# FULL_CB_Plugs_REV_C.net
KiCad netlist of a schematic drawn in Altium Designer
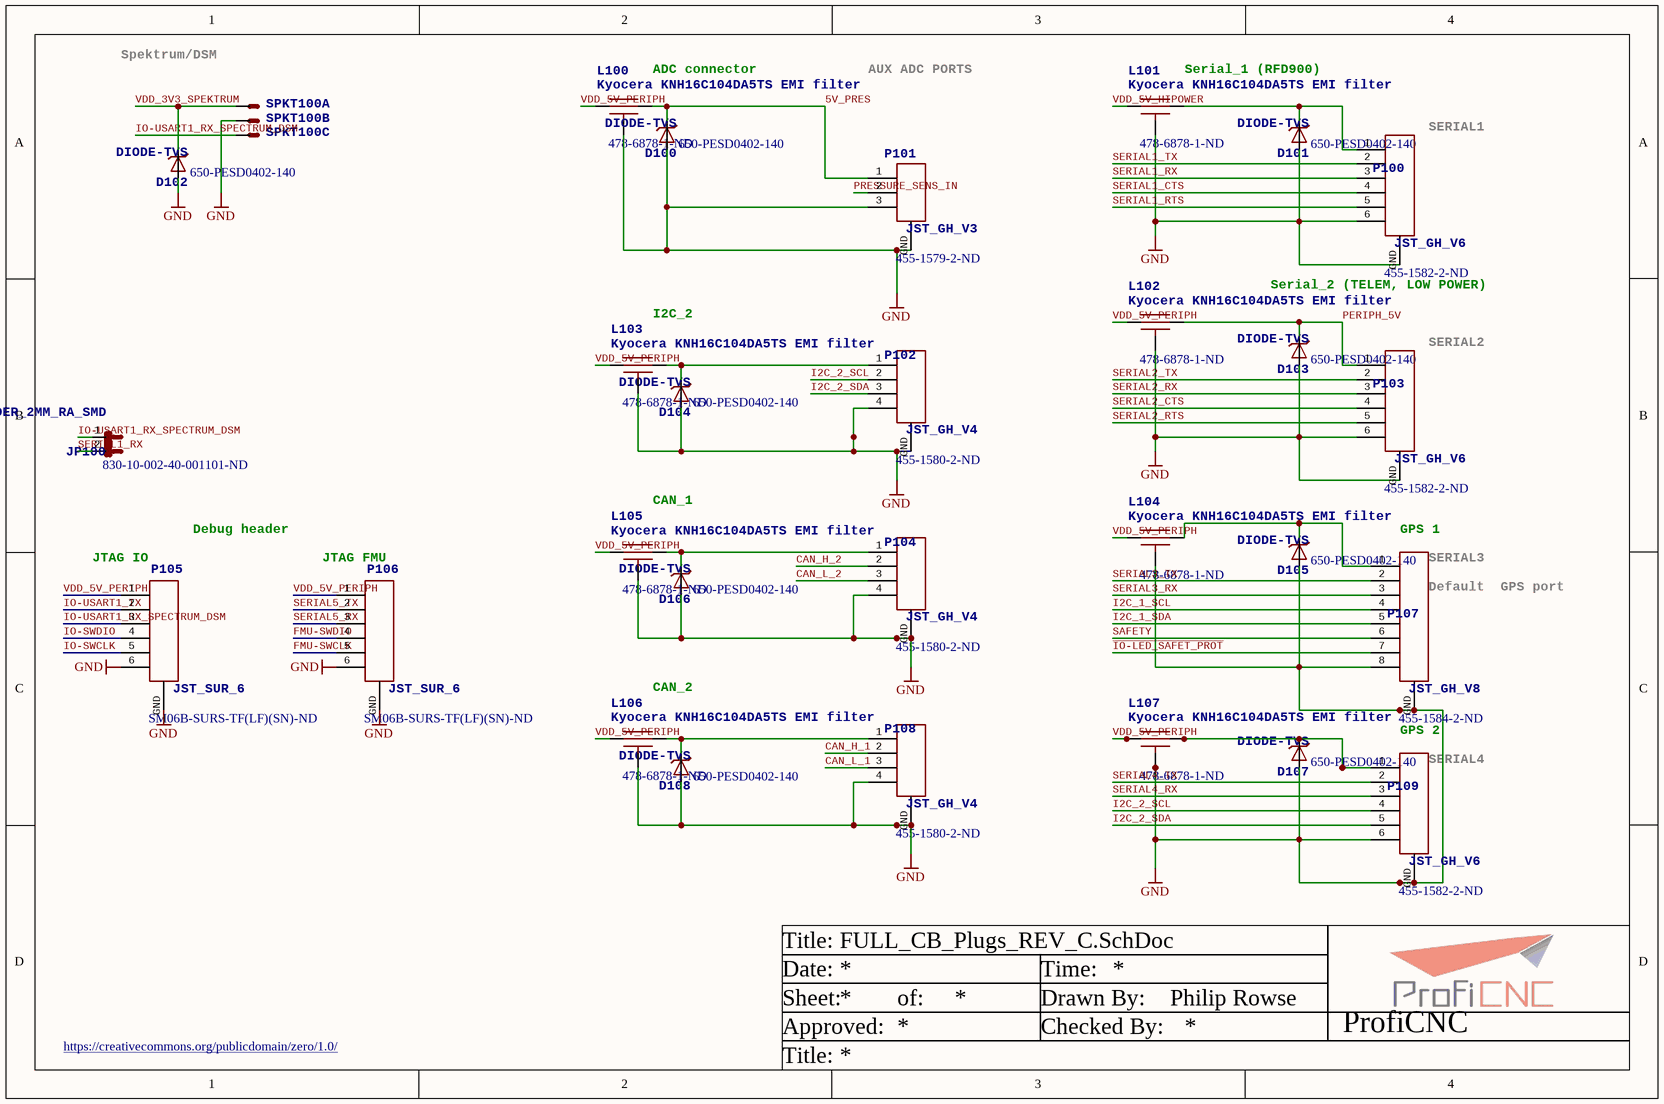
[diagram p0: FULL_CB_Plugs_REV_C.SchDoc]

(export (version "E")
  (design (tool "Eeschema 10.0.6"))
  (components
    (comp (ref "D100")
      (value "DIODE-TVS")
      (footprint "0402-TVS")
      (description "Diode, TVS, 14VWM, 40VC, 0402, SMD")
      (fields (field (name "SUPPLIER PART NUMBER 1") "650-PESD0402-140"))
      (libsource (lib "CB_REV_C") (part "DIODE-TVS"))
    )
    (comp (ref "D101")
      (value "DIODE-TVS")
      (footprint "0402-TVS")
      (description "Diode, TVS, 14VWM, 40VC, 0402, SMD")
      (fields (field (name "SUPPLIER PART NUMBER 1") "650-PESD0402-140"))
      (libsource (lib "CB_REV_C") (part "DIODE-TVS"))
    )
    (comp (ref "D102")
      (value "DIODE-TVS")
      (footprint "0402-TVS")
      (description "Diode, TVS, 14VWM, 40VC, 0402, SMD")
      (fields (field (name "SUPPLIER PART NUMBER 1") "650-PESD0402-140"))
      (libsource (lib "CB_REV_C") (part "DIODE-TVS"))
    )
    (comp (ref "D103")
      (value "DIODE-TVS")
      (footprint "0402-TVS")
      (description "Diode, TVS, 14VWM, 40VC, 0402, SMD")
      (fields (field (name "SUPPLIER PART NUMBER 1") "650-PESD0402-140"))
      (libsource (lib "CB_REV_C") (part "DIODE-TVS"))
    )
    (comp (ref "D104")
      (value "DIODE-TVS")
      (footprint "0402-TVS")
      (description "Diode, TVS, 14VWM, 40VC, 0402, SMD")
      (fields (field (name "SUPPLIER PART NUMBER 1") "650-PESD0402-140"))
      (libsource (lib "CB_REV_C") (part "DIODE-TVS"))
    )
    (comp (ref "D105")
      (value "DIODE-TVS")
      (footprint "0402-TVS")
      (description "Diode, TVS, 14VWM, 40VC, 0402, SMD")
      (fields (field (name "SUPPLIER PART NUMBER 1") "650-PESD0402-140"))
      (libsource (lib "CB_REV_C") (part "DIODE-TVS"))
    )
    (comp (ref "D106")
      (value "DIODE-TVS")
      (footprint "0402-TVS")
      (description "Diode, TVS, 14VWM, 40VC, 0402, SMD")
      (fields (field (name "SUPPLIER PART NUMBER 1") "650-PESD0402-140"))
      (libsource (lib "CB_REV_C") (part "DIODE-TVS"))
    )
    (comp (ref "D107")
      (value "DIODE-TVS")
      (footprint "0402-TVS")
      (description "Diode, TVS, 14VWM, 40VC, 0402, SMD")
      (fields (field (name "SUPPLIER PART NUMBER 1") "650-PESD0402-140"))
      (libsource (lib "CB_REV_C") (part "DIODE-TVS"))
    )
    (comp (ref "D108")
      (value "DIODE-TVS")
      (footprint "0402-TVS")
      (description "Diode, TVS, 14VWM, 40VC, 0402, SMD")
      (fields (field (name "SUPPLIER PART NUMBER 1") "650-PESD0402-140"))
      (libsource (lib "CB_REV_C") (part "DIODE-TVS"))
    )
    (comp (ref "JP100")
      (value "HEADER_2MM_RA_SMD")
      (footprint "HEADER_2MM_RA_2")
      (description "Connector, PCB, 2MM, 2Pos, R/A, SMD, Au")
      (fields (field (name "SUPPLIER PART NUMBER 1") "830-10-002-40-001101-ND"))
      (libsource (lib "CB_REV_C") (part "HEADER_2MM_RA_SMD"))
    )
    (comp (ref "L100")
      (value "Kyocera KNH16C104DA5TS EMI filter")
      (footprint "KYOCERA-KNH16-DA")
      (description "Capacitor, Filter, 0.1uF, 25V, 2A, 0603, SMD")
      (fields (field (name "SUPPLIER PART NUMBER 1") "478-6878-1-ND"))
      (libsource (lib "CB_REV_C") (part "KNH16C104DA5TS"))
    )
    (comp (ref "L101")
      (value "Kyocera KNH16C104DA5TS EMI filter")
      (footprint "KYOCERA-KNH16-DA")
      (description "Capacitor, Filter, 0.1uF, 25V, 2A, 0603, SMD")
      (fields (field (name "SUPPLIER PART NUMBER 1") "478-6878-1-ND"))
      (libsource (lib "CB_REV_C") (part "KNH16C104DA5TS"))
    )
    (comp (ref "L102")
      (value "Kyocera KNH16C104DA5TS EMI filter")
      (footprint "KYOCERA-KNH16-DA")
      (description "Capacitor, Filter, 0.1uF, 25V, 2A, 0603, SMD")
      (fields (field (name "SUPPLIER PART NUMBER 1") "478-6878-1-ND"))
      (libsource (lib "CB_REV_C") (part "KNH16C104DA5TS"))
    )
    (comp (ref "L103")
      (value "Kyocera KNH16C104DA5TS EMI filter")
      (footprint "KYOCERA-KNH16-DA")
      (description "Capacitor, Filter, 0.1uF, 25V, 2A, 0603, SMD")
      (fields (field (name "SUPPLIER PART NUMBER 1") "478-6878-1-ND"))
      (libsource (lib "CB_REV_C") (part "KNH16C104DA5TS"))
    )
    (comp (ref "L104")
      (value "Kyocera KNH16C104DA5TS EMI filter")
      (footprint "KYOCERA-KNH16-DA")
      (description "Capacitor, Filter, 0.1uF, 25V, 2A, 0603, SMD")
      (fields (field (name "SUPPLIER PART NUMBER 1") "478-6878-1-ND"))
      (libsource (lib "CB_REV_C") (part "KNH16C104DA5TS"))
    )
    (comp (ref "L105")
      (value "Kyocera KNH16C104DA5TS EMI filter")
      (footprint "KYOCERA-KNH16-DA")
      (description "Capacitor, Filter, 0.1uF, 25V, 2A, 0603, SMD")
      (fields (field (name "SUPPLIER PART NUMBER 1") "478-6878-1-ND"))
      (libsource (lib "CB_REV_C") (part "KNH16C104DA5TS"))
    )
    (comp (ref "L106")
      (value "Kyocera KNH16C104DA5TS EMI filter")
      (footprint "KYOCERA-KNH16-DA")
      (description "Capacitor, Filter, 0.1uF, 25V, 2A, 0603, SMD")
      (fields (field (name "SUPPLIER PART NUMBER 1") "478-6878-1-ND"))
      (libsource (lib "CB_REV_C") (part "KNH16C104DA5TS"))
    )
    (comp (ref "L107")
      (value "Kyocera KNH16C104DA5TS EMI filter")
      (footprint "KYOCERA-KNH16-DA")
      (description "Capacitor, Filter, 0.1uF, 25V, 2A, 0603, SMD")
      (fields (field (name "SUPPLIER PART NUMBER 1") "478-6878-1-ND"))
      (libsource (lib "CB_REV_C") (part "KNH16C104DA5TS"))
    )
    (comp (ref "P100")
      (value "JST_GH_V6")
      (footprint "JST_GH_V6")
      (description "BM06B-GHS-TBT")
      (fields (field (name "SUPPLIER PART NUMBER 1") "455-1582-2-ND"))
      (libsource (lib "CB_REV_C") (part "JST_GH_V6"))
    )
    (comp (ref "P101")
      (value "JST_GH_V3")
      (footprint "JST_GH_V3")
      (description "BM03B-GHS-TBT")
      (fields (field (name "SUPPLIER PART NUMBER 1") "455-1579-2-ND"))
      (libsource (lib "CB_REV_C") (part "JST_GH_V3"))
    )
    (comp (ref "P102")
      (value "JST_GH_V4")
      (footprint "JST_GH_V4")
      (description "BM04B-GHS-TBT")
      (fields (field (name "SUPPLIER PART NUMBER 1") "455-1580-2-ND"))
      (libsource (lib "CB_REV_C") (part "JST_GH_V4"))
    )
    (comp (ref "P103")
      (value "JST_GH_V6")
      (footprint "JST_GH_V6")
      (description "BM06B-GHS-TBT")
      (fields (field (name "SUPPLIER PART NUMBER 1") "455-1582-2-ND"))
      (libsource (lib "CB_REV_C") (part "JST_GH_V6"))
    )
    (comp (ref "P104")
      (value "JST_GH_V4")
      (footprint "JST_GH_V4")
      (description "BM04B-GHS-TBT")
      (fields (field (name "SUPPLIER PART NUMBER 1") "455-1580-2-ND"))
      (libsource (lib "CB_REV_C") (part "JST_GH_V4"))
    )
    (comp (ref "P105")
      (value "JST_SUR_6")
      (footprint "JST_SUR_H6")
      (description "Connector, Header, 6Pos, .8mm IDC, R/A, SMD, Tin")
      (fields (field (name "SUPPLIER PART NUMBER 1") "SM06B-SURS-TF(LF)(SN)-ND"))
      (libsource (lib "CB_REV_C") (part "JST_SUR_6"))
    )
    (comp (ref "P106")
      (value "JST_SUR_6")
      (footprint "JST_SUR_H6")
      (description "Connector, Header, 6Pos, .8mm IDC, R/A, SMD, Tin")
      (fields (field (name "SUPPLIER PART NUMBER 1") "SM06B-SURS-TF(LF)(SN)-ND"))
      (libsource (lib "CB_REV_C") (part "JST_SUR_6"))
    )
    (comp (ref "P107")
      (value "JST_GH_V8")
      (footprint "JST_GH_V8")
      (description "BM08B-GHS-TBT")
      (fields (field (name "SUPPLIER PART NUMBER 1") "455-1584-2-ND"))
      (libsource (lib "CB_REV_C") (part "JST_GH_V8"))
    )
    (comp (ref "P108")
      (value "JST_GH_V4")
      (footprint "JST_GH_V4")
      (description "BM04B-GHS-TBT")
      (fields (field (name "SUPPLIER PART NUMBER 1") "455-1580-2-ND"))
      (libsource (lib "CB_REV_C") (part "JST_GH_V4"))
    )
    (comp (ref "P109")
      (value "JST_GH_V6")
      (footprint "JST_GH_V6")
      (description "BM06B-GHS-TBT")
      (fields (field (name "SUPPLIER PART NUMBER 1") "455-1582-2-ND"))
      (libsource (lib "CB_REV_C") (part "JST_GH_V6"))
    )
    (comp (ref "SPKT100")
      (value "CONN_SPEKTRUM_RX-TH")
      (footprint "B3B-ZR")
      (description "Spektrum RX connector; JST ZH series S3B-ZR-SM4A-TF")
      (fields (field (name "PARTNO") "B3B-ZR(LF)(SN)"))
      (libsource (lib "CB_REV_C") (part "CONN_SPEKTRUM_RX-TH"))
    )
  )
  (nets
    (net (code "1") (name "/5V_PRES") (class "Default")
      (node (ref "D100") (pin "C") (pinfunction "C_C") (pintype "passive"))
      (node (ref "L100") (pin "P$2") (pinfunction "P$2_P$2") (pintype "passive"))
      (node (ref "P101") (pin "1") (pinfunction "1_1") (pintype "passive"))
    )
    (net (code "2") (name "/CAN_H_1") (class "Default")
      (node (ref "P108") (pin "2") (pinfunction "2_2") (pintype "passive"))
    )
    (net (code "3") (name "/CAN_H_2") (class "Default")
      (node (ref "P104") (pin "2") (pinfunction "2_2") (pintype "passive"))
    )
    (net (code "4") (name "/CAN_L_1") (class "Default")
      (node (ref "P108") (pin "3") (pinfunction "3_3") (pintype "passive"))
    )
    (net (code "5") (name "/CAN_L_2") (class "Default")
      (node (ref "P104") (pin "3") (pinfunction "3_3") (pintype "passive"))
    )
    (net (code "6") (name "/FMU-SWCLK") (class "Default")
      (node (ref "P106") (pin "5") (pinfunction "5_5") (pintype "passive"))
    )
    (net (code "7") (name "/FMU-SWDIO") (class "Default")
      (node (ref "P106") (pin "4") (pinfunction "4_4") (pintype "passive"))
    )
    (net (code "8") (name "/I2C_1_SCL") (class "Default")
      (node (ref "P107") (pin "4") (pinfunction "4_4") (pintype "passive"))
    )
    (net (code "9") (name "/I2C_1_SDA") (class "Default")
      (node (ref "P107") (pin "5") (pinfunction "5_5") (pintype "passive"))
    )
    (net (code "10") (name "/I2C_2_SCL") (class "Default")
      (node (ref "P102") (pin "2") (pinfunction "2_2") (pintype "passive"))
      (node (ref "P109") (pin "4") (pinfunction "4_4") (pintype "passive"))
    )
    (net (code "11") (name "/I2C_2_SDA") (class "Default")
      (node (ref "P102") (pin "3") (pinfunction "3_3") (pintype "passive"))
      (node (ref "P109") (pin "5") (pinfunction "5_5") (pintype "passive"))
    )
    (net (code "12") (name "/IO-SWCLK") (class "Default")
      (node (ref "P105") (pin "5") (pinfunction "5_5") (pintype "passive"))
    )
    (net (code "13") (name "/IO-SWDIO") (class "Default")
      (node (ref "P105") (pin "4") (pinfunction "4_4") (pintype "passive"))
    )
    (net (code "14") (name "/IO-USART1_RX_SPECTRUM_DSM") (class "Default")
      (node (ref "JP100") (pin "1") (pinfunction "1_1") (pintype "passive"))
      (node (ref "P105") (pin "3") (pinfunction "3_3") (pintype "passive"))
      (node (ref "SPKT100") (pin "1") (pinfunction "S_1") (pintype "passive"))
    )
    (net (code "15") (name "/IO-USART1_TX") (class "Default")
      (node (ref "P105") (pin "2") (pinfunction "2_2") (pintype "passive"))
    )
    (net (code "16") (name "/PERIPH_5V") (class "Default")
      (node (ref "D103") (pin "C") (pinfunction "C_C") (pintype "passive"))
      (node (ref "L102") (pin "P$2") (pinfunction "P$2_P$2") (pintype "passive"))
      (node (ref "P103") (pin "1") (pinfunction "1_1") (pintype "passive"))
    )
    (net (code "17") (name "/PRESSURE_SENS_IN") (class "Default")
      (node (ref "P101") (pin "2") (pinfunction "2_2") (pintype "passive"))
    )
    (net (code "18") (name "/SAFETY") (class "Default")
      (node (ref "P107") (pin "6") (pinfunction "6_6") (pintype "passive"))
    )
    (net (code "19") (name "/SERIAL1_CTS") (class "Default")
      (node (ref "P100") (pin "4") (pinfunction "4_4") (pintype "passive"))
    )
    (net (code "20") (name "/SERIAL1_RTS") (class "Default")
      (node (ref "P100") (pin "5") (pinfunction "5_5") (pintype "passive"))
    )
    (net (code "21") (name "/SERIAL1_RX") (class "Default")
      (node (ref "JP100") (pin "2") (pinfunction "2_2") (pintype "passive"))
      (node (ref "P100") (pin "3") (pinfunction "3_3") (pintype "passive"))
    )
    (net (code "22") (name "/SERIAL1_TX") (class "Default")
      (node (ref "P100") (pin "2") (pinfunction "2_2") (pintype "passive"))
    )
    (net (code "23") (name "/SERIAL2_CTS") (class "Default")
      (node (ref "P103") (pin "4") (pinfunction "4_4") (pintype "passive"))
    )
    (net (code "24") (name "/SERIAL2_RTS") (class "Default")
      (node (ref "P103") (pin "5") (pinfunction "5_5") (pintype "passive"))
    )
    (net (code "25") (name "/SERIAL2_RX") (class "Default")
      (node (ref "P103") (pin "3") (pinfunction "3_3") (pintype "passive"))
    )
    (net (code "26") (name "/SERIAL2_TX") (class "Default")
      (node (ref "P103") (pin "2") (pinfunction "2_2") (pintype "passive"))
    )
    (net (code "27") (name "/SERIAL3_RX") (class "Default")
      (node (ref "P107") (pin "3") (pinfunction "3_3") (pintype "passive"))
    )
    (net (code "28") (name "/SERIAL3_TX") (class "Default")
      (node (ref "P107") (pin "2") (pinfunction "2_2") (pintype "passive"))
    )
    (net (code "29") (name "/SERIAL4_RX") (class "Default")
      (node (ref "P109") (pin "3") (pinfunction "3_3") (pintype "passive"))
    )
    (net (code "30") (name "/SERIAL4_TX") (class "Default")
      (node (ref "P109") (pin "2") (pinfunction "2_2") (pintype "passive"))
    )
    (net (code "31") (name "/SERIAL5_RX") (class "Default")
      (node (ref "P106") (pin "3") (pinfunction "3_3") (pintype "passive"))
    )
    (net (code "32") (name "/SERIAL5_TX") (class "Default")
      (node (ref "P106") (pin "2") (pinfunction "2_2") (pintype "passive"))
    )
    (net (code "33") (name "/VDD_3V3_SPEKTRUM") (class "Default")
      (node (ref "D102") (pin "C") (pinfunction "C_C") (pintype "passive"))
      (node (ref "SPKT100") (pin "3") (pinfunction "S_3") (pintype "passive"))
    )
    (net (code "34") (name "/VDD_5V_HIPOWER") (class "Default")
      (node (ref "L101") (pin "P$1") (pinfunction "P$1_P$1") (pintype "passive"))
    )
    (net (code "35") (name "/VDD_5V_PERIPH") (class "Default")
      (node (ref "L100") (pin "P$1") (pinfunction "P$1_P$1") (pintype "passive"))
      (node (ref "L102") (pin "P$1") (pinfunction "P$1_P$1") (pintype "passive"))
      (node (ref "L103") (pin "P$1") (pinfunction "P$1_P$1") (pintype "passive"))
      (node (ref "L104") (pin "P$1") (pinfunction "P$1_P$1") (pintype "passive"))
      (node (ref "L105") (pin "P$1") (pinfunction "P$1_P$1") (pintype "passive"))
      (node (ref "L106") (pin "P$1") (pinfunction "P$1_P$1") (pintype "passive"))
      (node (ref "L107") (pin "P$1") (pinfunction "P$1_P$1") (pintype "passive"))
      (node (ref "P105") (pin "1") (pinfunction "1_1") (pintype "passive"))
      (node (ref "P106") (pin "1") (pinfunction "1_1") (pintype "passive"))
    )
    (net (code "36") (name "/~{IO-LED_SAFET_PROT}") (class "Default")
      (node (ref "P107") (pin "7") (pinfunction "7_7") (pintype "passive"))
    )
    (net (code "37") (name "GND") (class "Default")
      (node (ref "D100") (pin "A") (pinfunction "A_A") (pintype "passive"))
      (node (ref "D101") (pin "A") (pinfunction "A_A") (pintype "passive"))
      (node (ref "D102") (pin "A") (pinfunction "A_A") (pintype "passive"))
      (node (ref "D103") (pin "A") (pinfunction "A_A") (pintype "passive"))
      (node (ref "D104") (pin "A") (pinfunction "A_A") (pintype "passive"))
      (node (ref "D105") (pin "A") (pinfunction "A_A") (pintype "passive"))
      (node (ref "D106") (pin "A") (pinfunction "A_A") (pintype "passive"))
      (node (ref "D107") (pin "A") (pinfunction "A_A") (pintype "passive"))
      (node (ref "D108") (pin "A") (pinfunction "A_A") (pintype "passive"))
      (node (ref "L100") (pin "GND") (pinfunction "GND_GND") (pintype "passive"))
      (node (ref "L101") (pin "GND") (pinfunction "GND_GND") (pintype "passive"))
      (node (ref "L102") (pin "GND") (pinfunction "GND_GND") (pintype "passive"))
      (node (ref "L103") (pin "GND") (pinfunction "GND_GND") (pintype "passive"))
      (node (ref "L104") (pin "GND") (pinfunction "GND_GND") (pintype "passive"))
      (node (ref "L105") (pin "GND") (pinfunction "GND_GND") (pintype "passive"))
      (node (ref "L106") (pin "GND") (pinfunction "GND_GND") (pintype "passive"))
      (node (ref "L107") (pin "GND") (pinfunction "GND_GND") (pintype "passive"))
      (node (ref "P100") (pin "6") (pinfunction "6_6") (pintype "passive"))
      (node (ref "P100") (pin "GND") (pinfunction "GND_GND") (pintype "passive"))
      (node (ref "P101") (pin "3") (pinfunction "3_3") (pintype "passive"))
      (node (ref "P101") (pin "GND") (pinfunction "GND_GND") (pintype "passive"))
      (node (ref "P102") (pin "4") (pinfunction "4_4") (pintype "passive"))
      (node (ref "P102") (pin "GND") (pinfunction "GND_GND") (pintype "passive"))
      (node (ref "P103") (pin "6") (pinfunction "6_6") (pintype "passive"))
      (node (ref "P103") (pin "GND") (pinfunction "GND_GND") (pintype "passive"))
      (node (ref "P104") (pin "4") (pinfunction "4_4") (pintype "passive"))
      (node (ref "P104") (pin "GND") (pinfunction "GND_GND") (pintype "passive"))
      (node (ref "P105") (pin "6") (pinfunction "6_6") (pintype "passive"))
      (node (ref "P105") (pin "GND") (pinfunction "GND_GND") (pintype "passive"))
      (node (ref "P106") (pin "6") (pinfunction "6_6") (pintype "passive"))
      (node (ref "P106") (pin "GND") (pinfunction "GND_GND") (pintype "passive"))
      (node (ref "P107") (pin "8") (pinfunction "8_8") (pintype "passive"))
      (node (ref "P107") (pin "GND") (pinfunction "GND_GND") (pintype "passive"))
      (node (ref "P108") (pin "4") (pinfunction "4_4") (pintype "passive"))
      (node (ref "P108") (pin "GND") (pinfunction "GND_GND") (pintype "passive"))
      (node (ref "P109") (pin "6") (pinfunction "6_6") (pintype "passive"))
      (node (ref "P109") (pin "GND") (pinfunction "GND_GND") (pintype "passive"))
      (node (ref "SPKT100") (pin "2") (pinfunction "S_2") (pintype "passive"))
    )
    (net (code "38") (name "Net-(D101-PadC)") (class "Default")
      (node (ref "D101") (pin "C") (pinfunction "C_C") (pintype "passive"))
      (node (ref "L101") (pin "P$2") (pinfunction "P$2_P$2") (pintype "passive"))
      (node (ref "P100") (pin "1") (pinfunction "1_1") (pintype "passive"))
    )
    (net (code "39") (name "Net-(D104-PadC)") (class "Default")
      (node (ref "D104") (pin "C") (pinfunction "C_C") (pintype "passive"))
      (node (ref "L103") (pin "P$2") (pinfunction "P$2_P$2") (pintype "passive"))
      (node (ref "P102") (pin "1") (pinfunction "1_1") (pintype "passive"))
    )
    (net (code "40") (name "Net-(D105-PadC)") (class "Default")
      (node (ref "D105") (pin "C") (pinfunction "C_C") (pintype "passive"))
      (node (ref "L104") (pin "P$2") (pinfunction "P$2_P$2") (pintype "passive"))
      (node (ref "P107") (pin "1") (pinfunction "1_1") (pintype "passive"))
    )
    (net (code "41") (name "Net-(D106-PadC)") (class "Default")
      (node (ref "D106") (pin "C") (pinfunction "C_C") (pintype "passive"))
      (node (ref "L105") (pin "P$2") (pinfunction "P$2_P$2") (pintype "passive"))
      (node (ref "P104") (pin "1") (pinfunction "1_1") (pintype "passive"))
    )
    (net (code "42") (name "Net-(D107-PadC)") (class "Default")
      (node (ref "D107") (pin "C") (pinfunction "C_C") (pintype "passive"))
      (node (ref "L107") (pin "P$2") (pinfunction "P$2_P$2") (pintype "passive"))
      (node (ref "P109") (pin "1") (pinfunction "1_1") (pintype "passive"))
    )
    (net (code "43") (name "Net-(D108-PadC)") (class "Default")
      (node (ref "D108") (pin "C") (pinfunction "C_C") (pintype "passive"))
      (node (ref "L106") (pin "P$2") (pinfunction "P$2_P$2") (pintype "passive"))
      (node (ref "P108") (pin "1") (pinfunction "1_1") (pintype "passive"))
    )
  )
)
